# Sheet1.net
KiCad netlist of a schematic drawn in Altium Designer
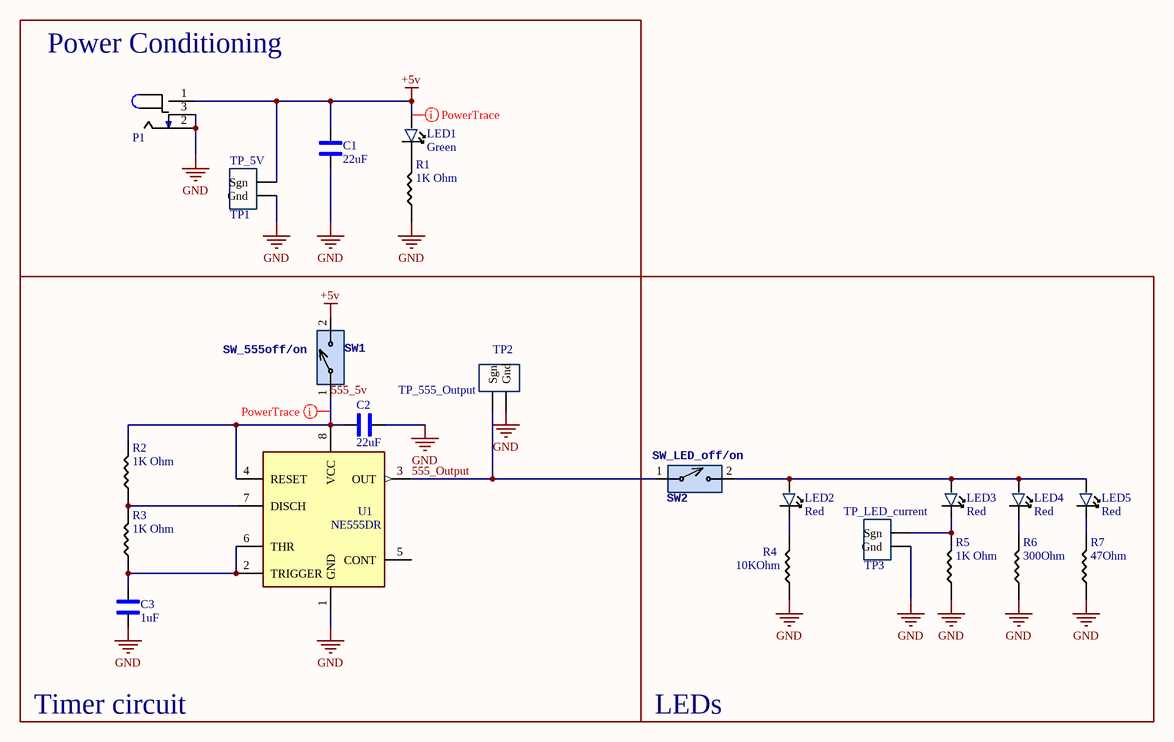
[diagram p0: Sheet1.SchDoc]

(export (version "E")
  (design (tool "Eeschema 10.0.6"))
  (components
    (comp (ref "C1")
      (value "22uF")
      (footprint "1206_Passive_Capacitor")
      (description "22uF ±10% 25V X5R 1206 Multilayer Ceramic Capacitors MLCC - SMD/SMT RoHS")
      (fields (field (name "MFR PART #") "CL31A226KAHNNNE") (field (name "LCSC PART#") "C12891"))
      (libsource (lib "ECEN5730Lib_JLC_2021_08") (part "C_22uF_1206"))
    )
    (comp (ref "C2")
      (value "22uF")
      (footprint "1206_Passive_Capacitor")
      (description "22uF ±10% 25V X5R 1206 Multilayer Ceramic Capacitors MLCC - SMD/SMT RoHS")
      (fields (field (name "MFR PART #") "CL31A226KAHNNNE") (field (name "LCSC PART#") "C12891"))
      (libsource (lib "ECEN5730Lib_JLC_2021_08") (part "C_22uF_1206"))
    )
    (comp (ref "C3")
      (value "1uF")
      (footprint "1206_Passive_Capacitor")
      (description "MULTILAYER CERAMIC CAPACITORS MLCC - SMD/SMT 1UF 50V 1206 ROHS")
      (fields (field (name "DIGIKEY PART") "399-8150-1-ND") (field (name "MFR PART #") "CL31B105KBHNNNE"))
      (libsource (lib "ECEN5730Lib_JLC_2021_08") (part "C_1uF_1206"))
    )
    (comp (ref "LED1")
      (value "Green")
      (footprint "LED_0603")
      (description "LIGHT EMITTING DIODES (LED) GREEN 520~535NM 112~258MCD@20MA TOP VIEW 0603 ROHS")
      (fields (field (name "MFR PART #") "19-217/GHC-YR1S2/3T") (field (name "LCSC PART#") "C72043"))
      (libsource (lib "ECEN5730Lib_JLC_2021_08") (part "LED_GREEN_0603"))
    )
    (comp (ref "LED2")
      (value "Red")
      (footprint "LED_1206")
      (description "Red 621~631nm 1206 Light Emitting Diodes (LED) RoHS")
      (fields (field (name "MFR PART #") "15-21/R6C-FQ1R1B/2T") (field (name "LCSC PART#") "C93133"))
      (libsource (lib "ECEN5730Lib_JLC_2021_08") (part "LED_RED_1206"))
    )
    (comp (ref "LED3")
      (value "Red")
      (footprint "LED_1206")
      (description "Red 621~631nm 1206 Light Emitting Diodes (LED) RoHS")
      (fields (field (name "MFR PART #") "15-21/R6C-FQ1R1B/2T") (field (name "LCSC PART#") "C93133"))
      (libsource (lib "ECEN5730Lib_JLC_2021_08") (part "LED_RED_1206"))
    )
    (comp (ref "LED4")
      (value "Red")
      (footprint "LED_1206")
      (description "Red 621~631nm 1206 Light Emitting Diodes (LED) RoHS")
      (fields (field (name "MFR PART #") "15-21/R6C-FQ1R1B/2T") (field (name "LCSC PART#") "C93133"))
      (libsource (lib "ECEN5730Lib_JLC_2021_08") (part "LED_RED_1206"))
    )
    (comp (ref "LED5")
      (value "Red")
      (footprint "LED_1206")
      (description "Red 621~631nm 1206 Light Emitting Diodes (LED) RoHS")
      (fields (field (name "MFR PART #") "15-21/R6C-FQ1R1B/2T") (field (name "LCSC PART#") "C93133"))
      (libsource (lib "ECEN5730Lib_JLC_2021_08") (part "LED_RED_1206"))
    )
    (comp (ref "P1")
      (value "Power Jack")
      (footprint "Power_Jack")
      (description "Power Barrel Connector Jack 2.10mm ID (0.083\"), 5.50mm OD (0.217\") Through Hole, Right Angle")
      (fields (field (name "DIGIKEY PART") "CP-102A-ND") (field (name "LCSC PART#") "C136744"))
      (libsource (lib "ECEN5730Lib_JLC_2021_08") (part "P_Power Jack"))
    )
    (comp (ref "R1")
      (value "1K Ohm")
      (footprint "0805_Passive_Resistor")
      (description "CHIP RESISTOR - SURFACE MOUNT 1KOHMS ±1% 1/8W 0805 ROHS")
      (fields (field (name "LCSC PART#") "C17513") (field (name "MFR PART #") "0805W8F1001T5E"))
      (libsource (lib "ECEN5730Lib_JLC_2021_08") (part "R_1K_0805"))
    )
    (comp (ref "R2")
      (value "1K Ohm")
      (footprint "0805_Passive_Resistor")
      (description "CHIP RESISTOR - SURFACE MOUNT 1KOHMS ±1% 1/8W 0805 ROHS")
      (fields (field (name "LCSC PART#") "C17513") (field (name "MFR PART #") "0805W8F1001T5E"))
      (libsource (lib "ECEN5730Lib_JLC_2021_08") (part "R_1K_0805"))
    )
    (comp (ref "R3")
      (value "1K Ohm")
      (footprint "0805_Passive_Resistor")
      (description "CHIP RESISTOR - SURFACE MOUNT 1KOHMS ±1% 1/8W 0805 ROHS")
      (fields (field (name "LCSC PART#") "C17513") (field (name "MFR PART #") "0805W8F1001T5E"))
      (libsource (lib "ECEN5730Lib_JLC_2021_08") (part "R_1K_0805"))
    )
    (comp (ref "R4")
      (value "10KOhm")
      (footprint "1206_Passive_Resitor")
      (description "10 kOhms ±5% 0.25W, 1/4W Chip Resistor 1206 (3216 Metric) Automotive AEC-Q200 Thick Film")
      (fields (field (name "DIGIKEY PART") "RMCF1206JT300RCT-ND") (field (name "LCSC PART#") "C17902"))
      (libsource (lib "ECEN5730Lib_JLC_2021_08") (part "R_10KOhm_1206"))
    )
    (comp (ref "R5")
      (value "1K Ohm")
      (footprint "0805_Passive_Resistor")
      (description "CHIP RESISTOR - SURFACE MOUNT 1KOHMS ±1% 1/8W 0805 ROHS")
      (fields (field (name "LCSC PART#") "C17513") (field (name "MFR PART #") "0805W8F1001T5E"))
      (libsource (lib "ECEN5730Lib_JLC_2021_08") (part "R_1K_0805"))
    )
    (comp (ref "R6")
      (value "300Ohm")
      (footprint "1206_Passive_Resitor")
      (description "CHIP RESISTOR - SURFACE MOUNT 300OHMS ±1% 1/4W 1206 ROHS")
      (fields (field (name "MFR PART #") "1206W4F3000T5E") (field (name "LCSC PART#") "C17887"))
      (libsource (lib "ECEN5730Lib_JLC_2021_08") (part "R_300Ohm_1206"))
    )
    (comp (ref "R7")
      (value "47Ohm")
      (footprint "1206_Passive_Resitor")
      (description "47Ω ±5% 0.25W ±200ppm/℃ 1206 Chip Resistor - Surface Mount RoHS")
      (fields (field (name "MFR PART #") "1206W4J0470T5E") (field (name "LCSC PART#") "C25384"))
      (libsource (lib "ECEN5730Lib_JLC_2021_08") (part "R_47Ohm_1206"))
    )
    (comp (ref "SW1")
      (value "SW_555off/on")
      (footprint "2Pin-Header-Conn")
      (description "2Pin Header")
      (fields (field (name "LCSC PART#") "C124375"))
      (libsource (lib "") (part "SW_2Pin_100mil_Switch_1"))
    )
    (comp (ref "SW2")
      (value "SW_LED_off/on")
      (footprint "2Pin-Header-Conn")
      (description "2Pin Header")
      (fields (field (name "LCSC PART#") "C124375"))
      (libsource (lib "ECEN5730Lib_JLC_2021_08") (part "SW_2Pin_100mil_Switch"))
    )
    (comp (ref "TP1")
      (value "TP_5V")
      (footprint "TP10x_Probe")
      (description "Test Point 300 mil centers")
      (libsource (lib "ECEN5730Lib_Manual_2021_08") (part "TP_10x_Probe"))
    )
    (comp (ref "TP2")
      (value "TP_555_Output")
      (footprint "TP10x_Probe")
      (description "Test Point 300 mil centers")
      (libsource (lib "") (part "TP_10x_Probe_1"))
    )
    (comp (ref "TP3")
      (value "TP_LED_current")
      (footprint "TP10x_Probe")
      (description "Test Point 300 mil centers")
      (libsource (lib "ECEN5730Lib_Manual_2021_08") (part "TP_10x_Probe"))
    )
    (comp (ref "U1")
      (value "NE555DR")
      (footprint "TS555IDTTR")
      (description "555 Timer SOIC-8_150MIL ROHS 150ns Rise Time")
      (fields (field (name "LCSC PART#") "C7593"))
      (libsource (lib "ECEN5730Lib_JLC_2021_08") (part "U_555_Slow"))
    )
  )
  (nets
    (net (code "1") (name "+5v") (class "Default")
      (node (ref "C1") (pin "2") (pinfunction "2_2") (pintype "passive"))
      (node (ref "LED1") (pin "1") (pinfunction "1_1") (pintype "passive"))
      (node (ref "P1") (pin "1") (pinfunction "1_1") (pintype "power_in"))
      (node (ref "SW1") (pin "2") (pinfunction "2_2") (pintype "passive"))
      (node (ref "TP1") (pin "1") (pinfunction "Sgn_1") (pintype "passive"))
    )
    (net (code "2") (name "/555_5v") (class "Default")
      (node (ref "C2") (pin "2") (pinfunction "2_2") (pintype "passive"))
      (node (ref "R2") (pin "2") (pinfunction "2_2") (pintype "passive"))
      (node (ref "SW1") (pin "1") (pinfunction "1_1") (pintype "passive"))
      (node (ref "U1") (pin "4") (pinfunction "RESET_4") (pintype "passive"))
      (node (ref "U1") (pin "8") (pinfunction "VCC_8") (pintype "power_in"))
    )
    (net (code "3") (name "/555_Output") (class "Default")
      (node (ref "SW2") (pin "1") (pinfunction "1_1") (pintype "passive"))
      (node (ref "TP2") (pin "1") (pinfunction "Sgn_1") (pintype "passive"))
      (node (ref "U1") (pin "3") (pinfunction "OUT_3") (pintype "output"))
    )
    (net (code "4") (name "GND") (class "Default")
      (node (ref "C1") (pin "1") (pinfunction "1_1") (pintype "passive"))
      (node (ref "C2") (pin "1") (pinfunction "1_1") (pintype "passive"))
      (node (ref "C3") (pin "1") (pinfunction "1_1") (pintype "passive"))
      (node (ref "P1") (pin "2") (pinfunction "2_2") (pintype "power_in"))
      (node (ref "P1") (pin "3") (pinfunction "3_3") (pintype "power_in"))
      (node (ref "R1") (pin "1") (pinfunction "1_1") (pintype "passive"))
      (node (ref "R4") (pin "1") (pinfunction "1_1") (pintype "passive"))
      (node (ref "R5") (pin "1") (pinfunction "1_1") (pintype "passive"))
      (node (ref "R6") (pin "1") (pinfunction "1_1") (pintype "passive"))
      (node (ref "R7") (pin "1") (pinfunction "1_1") (pintype "passive"))
      (node (ref "TP1") (pin "2") (pinfunction "Gnd_2") (pintype "passive"))
      (node (ref "TP2") (pin "2") (pinfunction "Gnd_2") (pintype "passive"))
      (node (ref "TP3") (pin "2") (pinfunction "Gnd_2") (pintype "passive"))
      (node (ref "U1") (pin "1") (pinfunction "GND_1") (pintype "power_in"))
    )
    (net (code "5") (name "Net-(LED1-Pad2)") (class "Default")
      (node (ref "LED1") (pin "2") (pinfunction "2_2") (pintype "passive"))
      (node (ref "R1") (pin "2") (pinfunction "2_2") (pintype "passive"))
    )
    (net (code "6") (name "Net-(LED2-Pad1)") (class "Default")
      (node (ref "LED2") (pin "1") (pinfunction "1_1") (pintype "passive"))
      (node (ref "LED3") (pin "1") (pinfunction "1_1") (pintype "passive"))
      (node (ref "LED4") (pin "1") (pinfunction "1_1") (pintype "passive"))
      (node (ref "LED5") (pin "1") (pinfunction "1_1") (pintype "passive"))
      (node (ref "SW2") (pin "2") (pinfunction "2_2") (pintype "passive"))
    )
    (net (code "7") (name "Net-(LED2-Pad2)") (class "Default")
      (node (ref "LED2") (pin "2") (pinfunction "2_2") (pintype "passive"))
      (node (ref "R4") (pin "2") (pinfunction "2_2") (pintype "passive"))
    )
    (net (code "8") (name "Net-(LED4-Pad2)") (class "Default")
      (node (ref "LED4") (pin "2") (pinfunction "2_2") (pintype "passive"))
      (node (ref "R6") (pin "2") (pinfunction "2_2") (pintype "passive"))
    )
    (net (code "9") (name "Net-(LED5-Pad2)") (class "Default")
      (node (ref "LED5") (pin "2") (pinfunction "2_2") (pintype "passive"))
      (node (ref "R7") (pin "2") (pinfunction "2_2") (pintype "passive"))
    )
    (net (code "10") (name "Net-(TP3-Sgn)") (class "Default")
      (node (ref "LED3") (pin "2") (pinfunction "2_2") (pintype "passive"))
      (node (ref "R5") (pin "2") (pinfunction "2_2") (pintype "passive"))
      (node (ref "TP3") (pin "1") (pinfunction "Sgn_1") (pintype "passive"))
    )
    (net (code "11") (name "Net-(U1-DISCH)") (class "Default")
      (node (ref "R2") (pin "1") (pinfunction "1_1") (pintype "passive"))
      (node (ref "R3") (pin "2") (pinfunction "2_2") (pintype "passive"))
      (node (ref "U1") (pin "7") (pinfunction "DISCH_7") (pintype "passive"))
    )
    (net (code "12") (name "Net-(U1-THR)") (class "Default")
      (node (ref "C3") (pin "2") (pinfunction "2_2") (pintype "passive"))
      (node (ref "R3") (pin "1") (pinfunction "1_1") (pintype "passive"))
      (node (ref "U1") (pin "2") (pinfunction "TRIGGER_2") (pintype "passive"))
      (node (ref "U1") (pin "6") (pinfunction "THR_6") (pintype "passive"))
    )
    (net (code "13") (name "unconnected-(U1-CONT-Pad5)") (class "Default")
      (node (ref "U1") (pin "5") (pinfunction "CONT_5") (pintype "passive"))
    )
  )
)
